# bpf-IF-SAW-856930.net
KiCad netlist of a schematic drawn in EAGLE
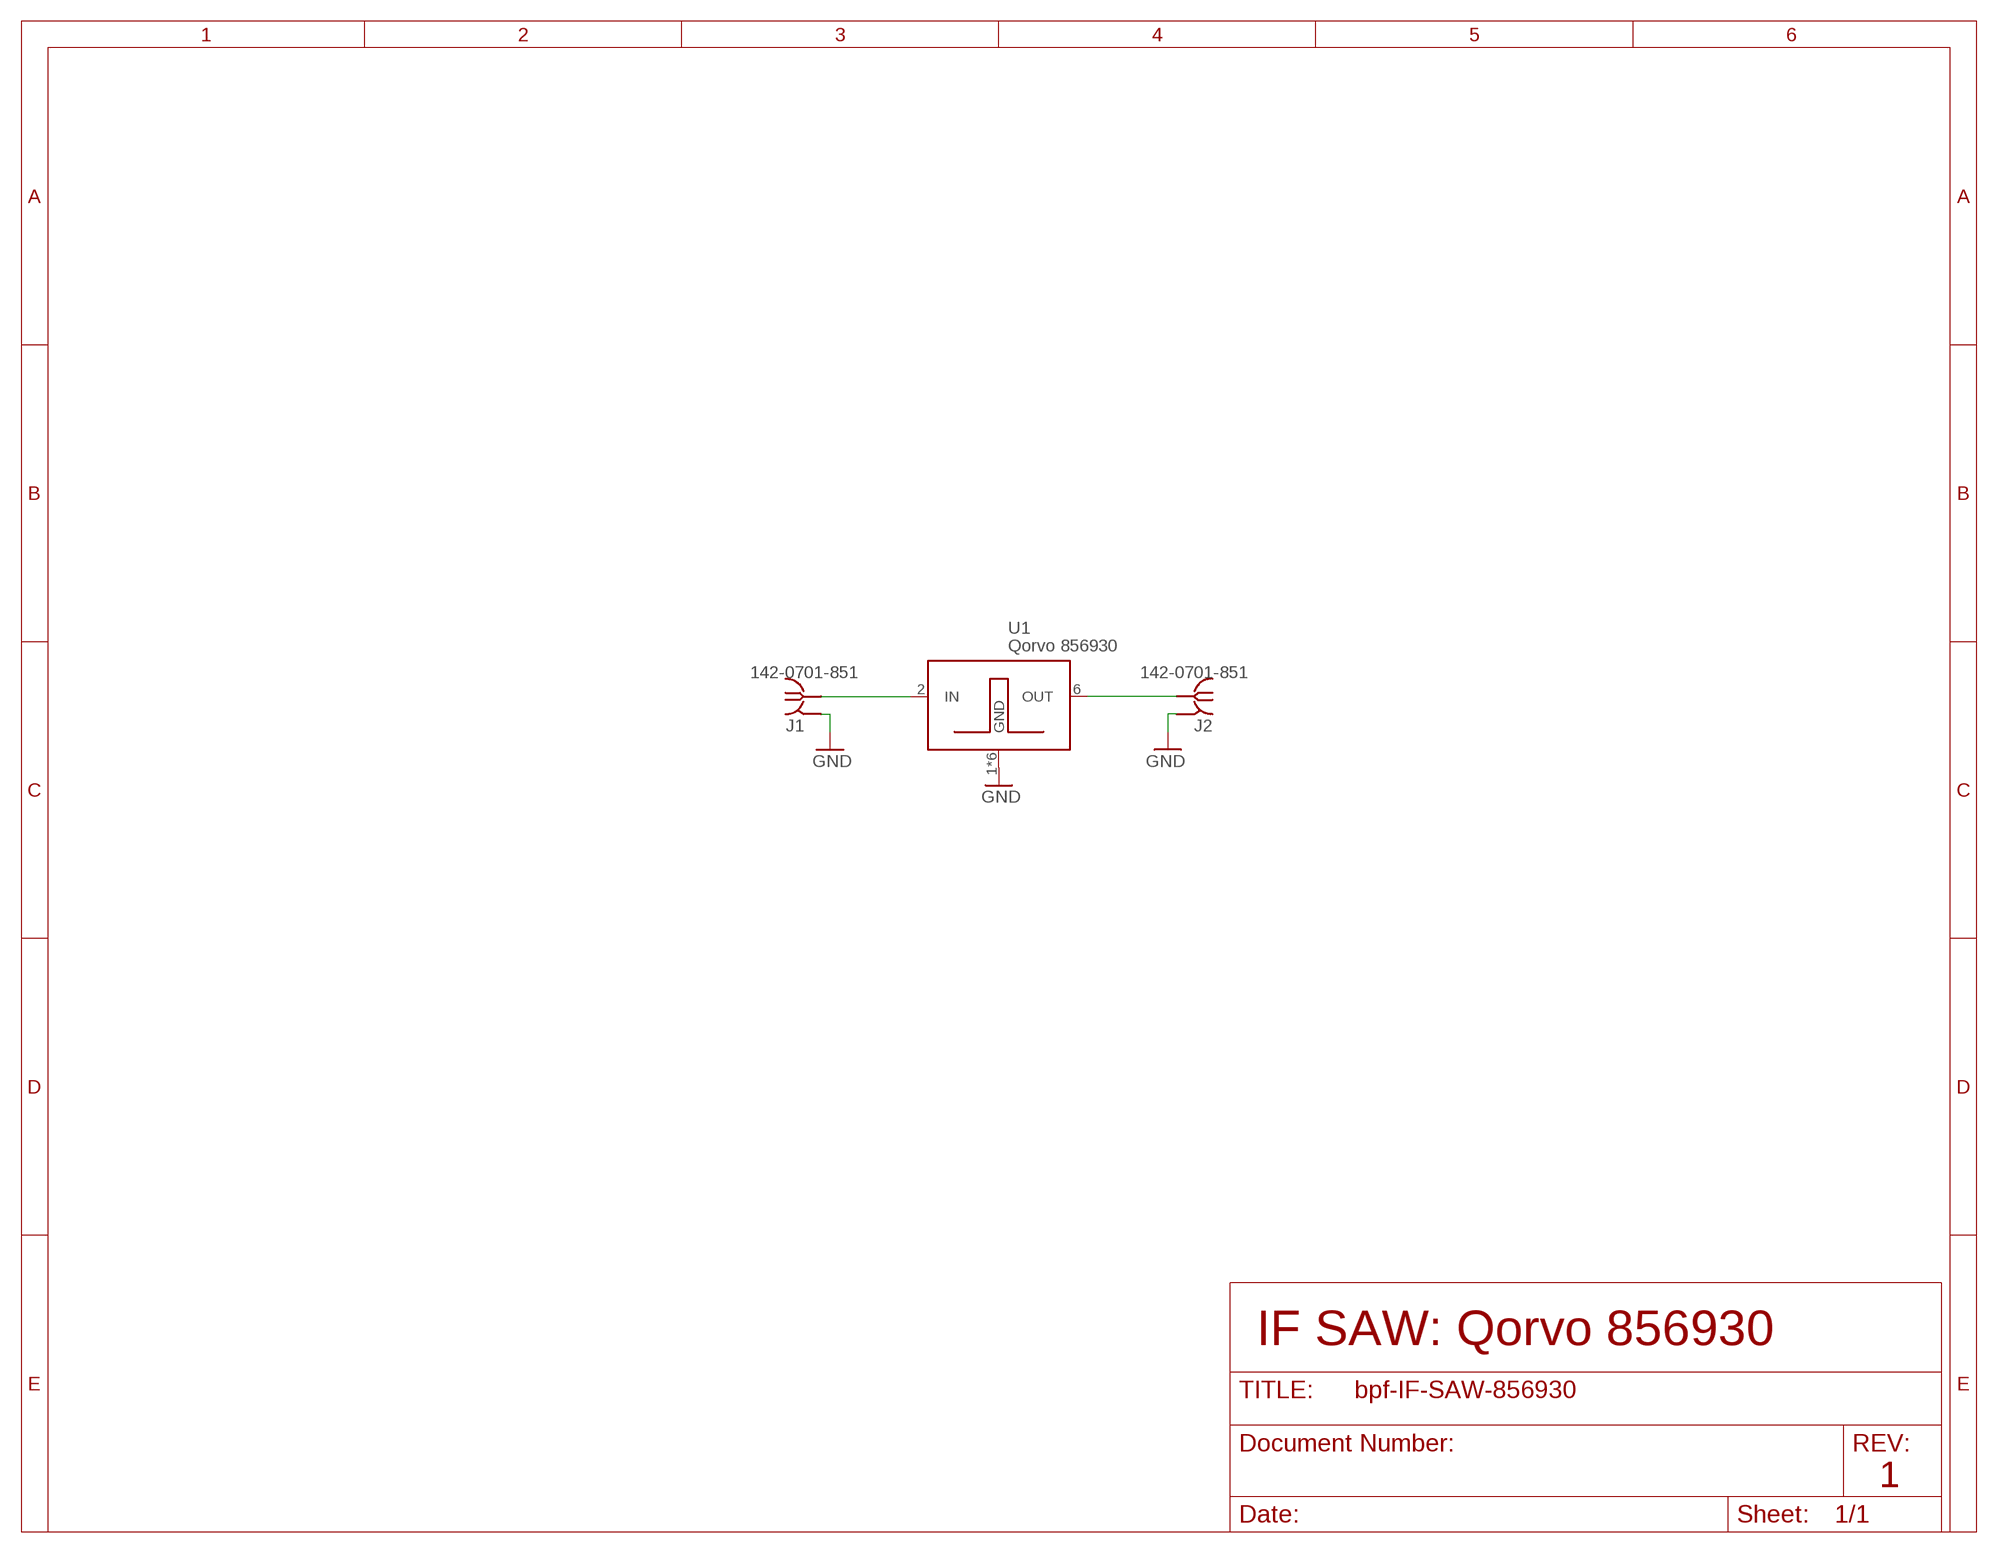
[diagram p0: schematic, sheet 1]

(export (version "E")
  (design (tool "Eeschema 10.0.6"))
  (components
    (comp (ref "J1")
      (value "142-0701-851")
      (footprint "eagle-import:142-0701-851")
      (libsource (lib "eagle-import") (part "142-0701-851"))
    )
    (comp (ref "J2")
      (value "142-0701-851")
      (footprint "eagle-import:142-0701-851")
      (libsource (lib "eagle-import") (part "142-0701-851"))
    )
    (comp (ref "U1")
      (value "Qorvo 856930")
      (footprint "eagle-import:3.8X3.8")
      (libsource (lib "eagle-import") (part "856930"))
    )
  )
  (nets
    (net (code "1") (name "GND") (class "Default")
      (node (ref "J1") (pin "GND1") (pinfunction "GND_GND1") (pintype "bidirectional"))
      (node (ref "J1") (pin "GND2") (pinfunction "GND_GND2") (pintype "bidirectional"))
      (node (ref "J1") (pin "GND3") (pinfunction "GND_GND3") (pintype "bidirectional"))
      (node (ref "J1") (pin "GND4") (pinfunction "GND_GND4") (pintype "bidirectional"))
      (node (ref "J2") (pin "GND1") (pinfunction "GND_GND1") (pintype "bidirectional"))
      (node (ref "J2") (pin "GND2") (pinfunction "GND_GND2") (pintype "bidirectional"))
      (node (ref "J2") (pin "GND3") (pinfunction "GND_GND3") (pintype "bidirectional"))
      (node (ref "J2") (pin "GND4") (pinfunction "GND_GND4") (pintype "bidirectional"))
      (node (ref "U1") (pin "1") (pinfunction "GND_1") (pintype "power_in"))
      (node (ref "U1") (pin "3") (pinfunction "GND_3") (pintype "power_in"))
      (node (ref "U1") (pin "4") (pinfunction "GND_4") (pintype "power_in"))
      (node (ref "U1") (pin "5") (pinfunction "GND_5") (pintype "power_in"))
      (node (ref "U1") (pin "7") (pinfunction "GND_7") (pintype "power_in"))
      (node (ref "U1") (pin "8") (pinfunction "GND_8") (pintype "power_in"))
    )
    (net (code "2") (name "Net-(J1-RF)") (class "Default")
      (node (ref "J1") (pin "RF1") (pinfunction "RF_RF1") (pintype "bidirectional"))
      (node (ref "U1") (pin "2") (pinfunction "IN_2") (pintype "input"))
    )
    (net (code "3") (name "Net-(J2-RF)") (class "Default")
      (node (ref "J2") (pin "RF1") (pinfunction "RF_RF1") (pintype "bidirectional"))
      (node (ref "U1") (pin "6") (pinfunction "OUT_6") (pintype "output"))
    )
  )
)
